# Sheet3.net
KiCad netlist of a schematic drawn in Altium Designer
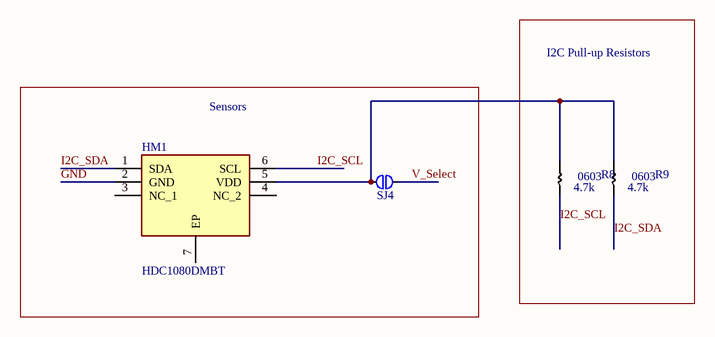
[diagram p0: Sheet3.SchDoc]

(export (version "E")
  (design (tool "Eeschema 10.0.6"))
  (components
    (comp (ref "HM1")
      (value "HDC1080DMBT")
      (footprint "SON100P300X300X80-7N")
      (description "Hygrometer")
      (fields
        (field (name "MOUSER PART NUMBER") "595-HDC1080DMBT")
        (field (name "RS PART NUMBER") "1330170P")
      )
      (libsource (lib "EnvironmentalSensor") (part "HDC1080DMBT"))
    )
    (comp (ref "R8")
      (value "4.7k")
      (footprint "0603_SMD")
      (libsource (lib "Enviornmental_Sensor") (part "R_0603"))
    )
    (comp (ref "R9")
      (value "4.7k")
      (footprint "0603_SMD")
      (libsource (lib "Enviornmental_Sensor") (part "R_0603"))
    )
    (comp (ref "SJ4")
      (value "Debug-Solder-Jumper")
      (footprint "DEBUG-SOLDER-JUMPER")
      (description "3.5mm Diameter, Solder Jumper Pad")
      (libsource (lib "MasterLib") (part "Debug-Solder-Jumper"))
    )
  )
  (nets
    (net (code "1") (name "/GND") (class "Default")
      (node (ref "HM1") (pin "2") (pinfunction "GND_2") (pintype "power_in"))
    )
    (net (code "2") (name "/I2C_SCL") (class "Default")
      (node (ref "HM1") (pin "6") (pinfunction "SCL_6") (pintype "passive"))
      (node (ref "R8") (pin "2") (pinfunction "2_2") (pintype "passive"))
    )
    (net (code "3") (name "/I2C_SDA") (class "Default")
      (node (ref "HM1") (pin "1") (pinfunction "SDA_1") (pintype "passive"))
      (node (ref "R9") (pin "2") (pinfunction "2_2") (pintype "passive"))
    )
    (net (code "4") (name "/V_Select") (class "Default")
      (node (ref "SJ4") (pin "2") (pinfunction "2_2") (pintype "passive"))
    )
    (net (code "5") (name "Net-(HM1-VDD)") (class "Default")
      (node (ref "HM1") (pin "5") (pinfunction "VDD_5") (pintype "power_in"))
      (node (ref "R8") (pin "1") (pinfunction "1_1") (pintype "passive"))
      (node (ref "R9") (pin "1") (pinfunction "1_1") (pintype "passive"))
      (node (ref "SJ4") (pin "1") (pinfunction "1_1") (pintype "passive"))
    )
    (net (code "6") (name "unconnected-(HM1-EP-Pad7)") (class "Default")
      (node (ref "HM1") (pin "7") (pinfunction "EP_7") (pintype "power_in"))
    )
    (net (code "7") (name "unconnected-(HM1-NC_1-Pad3)") (class "Default")
      (node (ref "HM1") (pin "3") (pinfunction "NC_1_3") (pintype "passive"))
    )
    (net (code "8") (name "unconnected-(HM1-NC_2-Pad4)") (class "Default")
      (node (ref "HM1") (pin "4") (pinfunction "NC_2_4") (pintype "passive"))
    )
  )
)
